# PWR_PAM2312_0V6_1A.net
KiCad netlist of a schematic drawn in Altium Designer
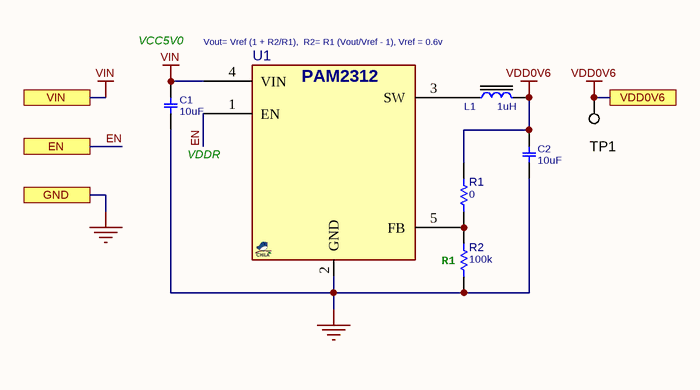
[diagram p0: PWR_PAM2312_0V6_1A.SchDoc]

(export (version "E")
  (design (tool "Eeschema 10.0.6"))
  (components
    (comp (ref "C1")
      (value "10uF")
      (footprint "C0402")
      (description "CAP, MLCC")
      (fields (field (name "MANF_P#") "CL05A106MP5NUNC") (field (name "MANF") "Samsung"))
      (libsource (lib "passive_smd") (part "CAP_SMD_MLCC"))
    )
    (comp (ref "C2")
      (value "10uF")
      (footprint "C0402")
      (description "CAP, MLCC")
      (fields (field (name "MANF_P#") "CL05A106MP5NUNC") (field (name "MANF") "Samsung"))
      (libsource (lib "passive_smd") (part "CAP_SMD_MLCC"))
    )
    (comp (ref "L1")
      (value "1uH")
      (footprint "L0805")
      (description "INDUCTOR")
      (fields (field (name "MANF_P#") "LQM21PN1R0MGHL"))
      (libsource (lib "chila_passive") (part "IND_SMD_2.2uH_4A"))
    )
    (comp (ref "R1")
      (value "0")
      (footprint "R0402")
      (description "RESISTOR, SMD, 20K, 0402")
      (libsource (lib "chila_passive") (part "RES_SMD"))
    )
    (comp (ref "R2")
      (value "100k")
      (footprint "R0402")
      (description "RESISTOR, SMD, 20K, 0402")
      (libsource (lib "chila_passive") (part "RES_SMD"))
    )
    (comp (ref "TP1")
      (value "TESTPOINT_SMD")
      (footprint "TPSMD_S1")
      (description "TEST POINT")
      (fields (field (name "MANF") "MANF") (field (name "MANF_P#") "MANF_P#"))
      (libsource (lib "test-tp_jumper") (part "TESTPOINT_SMD"))
    )
    (comp (ref "U1")
      (value "PAM2312")
      (footprint "SOT23_5")
      (description "REG, Switching, Buck, 1A, ADJ, 1.5MHz, 2.5~5.5VIN, SOT23-5")
      (fields (field (name "MANF") "Diodes") (field (name "MANF_P#") "PAM2312AABADJ"))
      (libsource (lib "pwr_switching_buck") (part "VREG_PAM2312_SOT23"))
    )
  )
  (nets
    (net (code "1") (name "/EN") (class "Default")
      (node (ref "U1") (pin "1") (pinfunction "EN_1") (pintype "power_in"))
    )
    (net (code "2") (name "GND") (class "Default")
      (node (ref "C1") (pin "1") (pinfunction "1_1") (pintype "passive"))
      (node (ref "C2") (pin "1") (pinfunction "1_1") (pintype "passive"))
      (node (ref "R2") (pin "2") (pinfunction "2_2") (pintype "passive"))
      (node (ref "U1") (pin "2") (pinfunction "GND_2") (pintype "power_in"))
    )
    (net (code "3") (name "Net-(U1-FB)") (class "Default")
      (node (ref "R1") (pin "2") (pinfunction "2_2") (pintype "passive"))
      (node (ref "R2") (pin "1") (pinfunction "1_1") (pintype "passive"))
      (node (ref "U1") (pin "5") (pinfunction "FB_5") (pintype "power_in"))
    )
    (net (code "4") (name "Net-(U1-SW)") (class "Default")
      (node (ref "L1") (pin "1") (pinfunction "1_1") (pintype "passive"))
      (node (ref "U1") (pin "3") (pinfunction "SW_3") (pintype "power_in"))
    )
    (net (code "5") (name "VDD0V6") (class "Default")
      (node (ref "C2") (pin "2") (pinfunction "2_2") (pintype "passive"))
      (node (ref "L1") (pin "2") (pinfunction "2_2") (pintype "passive"))
      (node (ref "R1") (pin "1") (pinfunction "1_1") (pintype "passive"))
      (node (ref "TP1") (pin "1") (pinfunction "1_1") (pintype "passive"))
    )
    (net (code "6") (name "VIN") (class "Default")
      (node (ref "C1") (pin "2") (pinfunction "2_2") (pintype "passive"))
      (node (ref "U1") (pin "4") (pinfunction "VIN_4") (pintype "power_in"))
    )
  )
)
